# esquema_eletrico_eagle.net
KiCad netlist of a schematic drawn in EAGLE
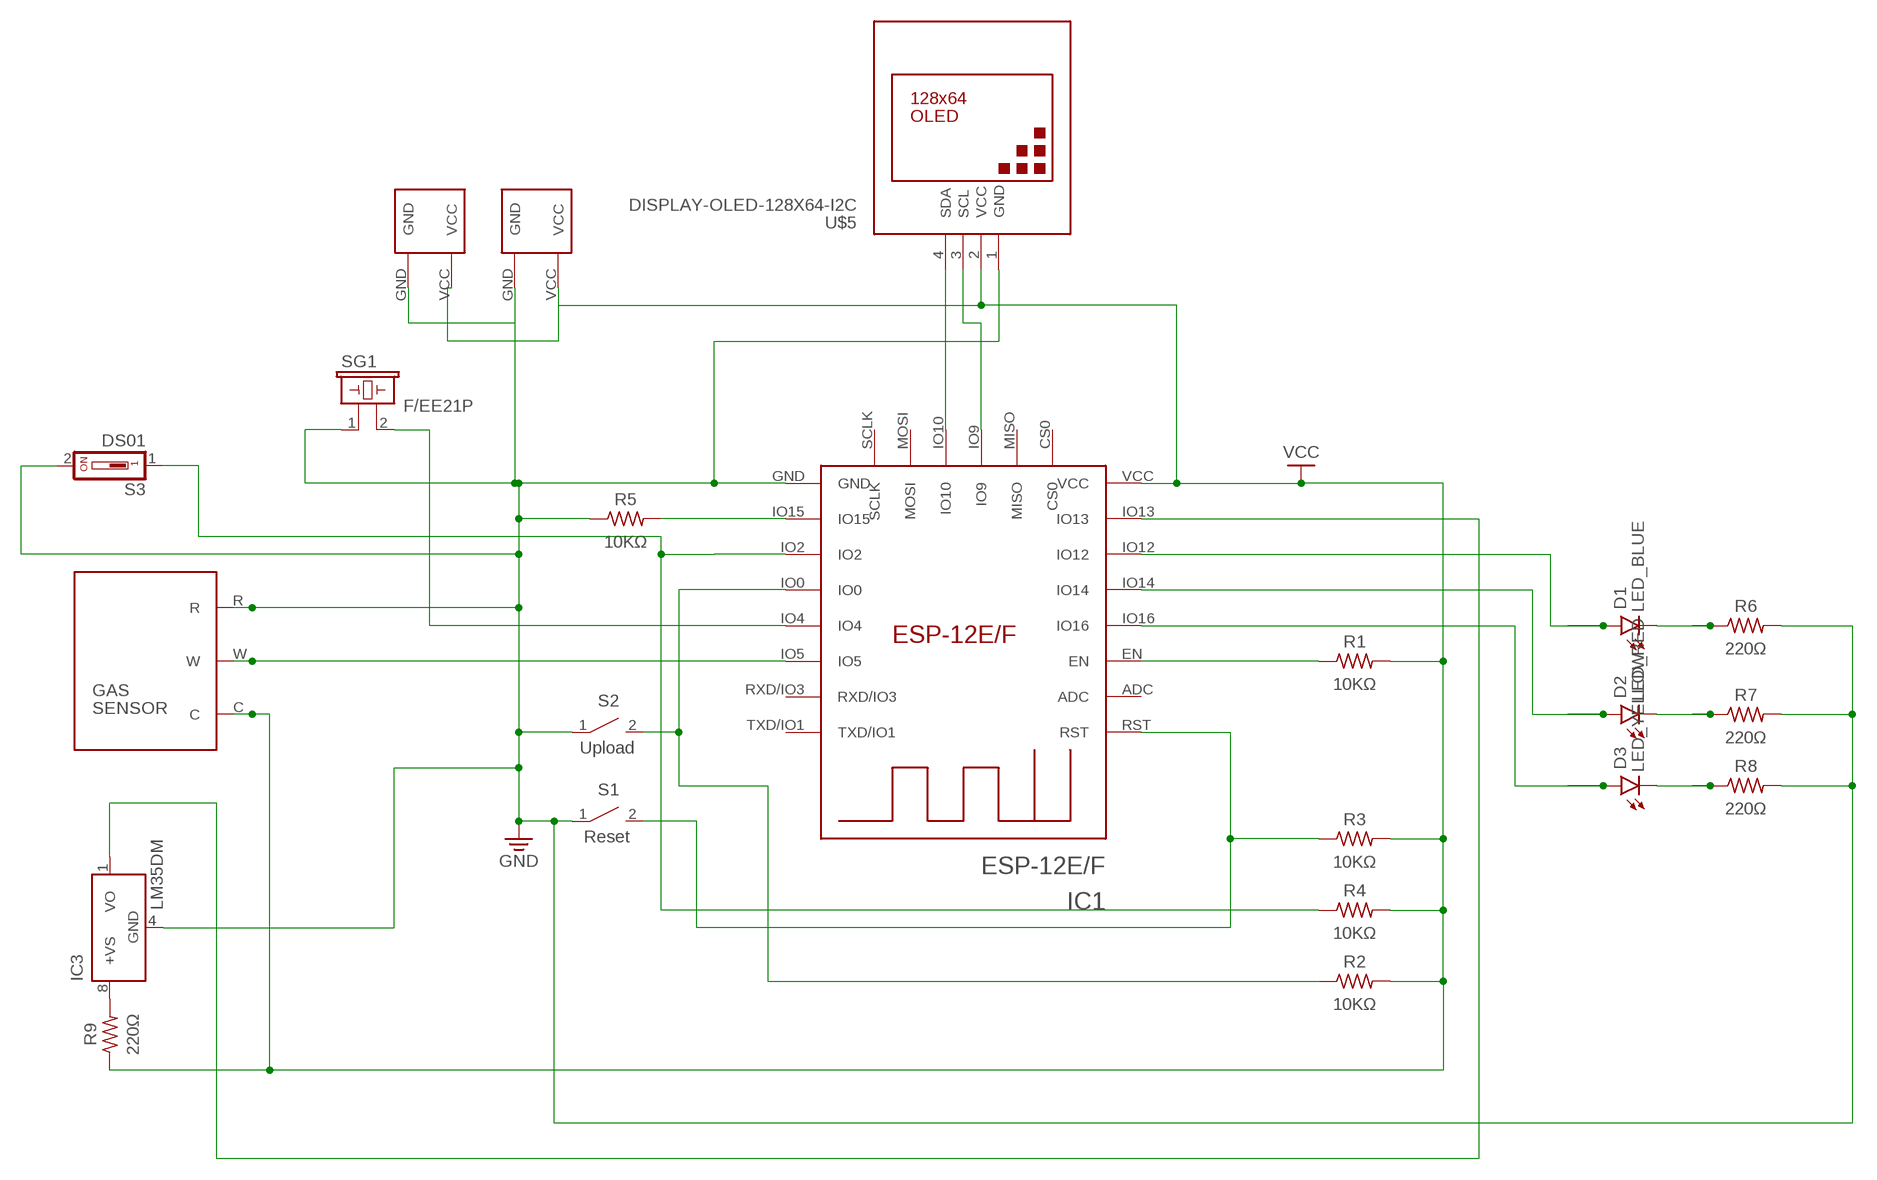
[diagram p0: schematic, sheet 1]

(export (version "E")
  (design (tool "Eeschema 10.0.6"))
  (components
    (comp (ref "D1")
      (value "LED_BLUE")
      (footprint "eagle-import:LEDRD254W60D565H860B_B")
      (libsource (lib "eagle-import") (part "LED_RADIALBLUE_"))
    )
    (comp (ref "D2")
      (value "LED_RED")
      (footprint "eagle-import:LEDRD254W60D565H860B")
      (libsource (lib "eagle-import") (part "LED_RADIALRED_"))
    )
    (comp (ref "D3")
      (value "LED_YELLOW")
      (footprint "eagle-import:LEDRD254W60D565H860B_Y")
      (libsource (lib "eagle-import") (part "LED_RADIALYELLOW_"))
    )
    (comp (ref "IC1")
      (value "ESP-12E/F")
      (footprint "eagle-import:ESP-12E")
      (libsource (lib "eagle-import") (part "ESP-12E/F"))
    )
    (comp (ref "IC3")
      (value "LM35DM")
      (footprint "eagle-import:SO08")
      (libsource (lib "eagle-import") (part "LM35DM"))
    )
    (comp (ref "R1")
      (value "10KΩ")
      (footprint "eagle-import:RESAD724W46L381D178B")
      (libsource (lib "eagle-import") (part "R-USAXIAL-7.2MM-PITCH_"))
    )
    (comp (ref "R2")
      (value "10KΩ")
      (footprint "eagle-import:RESAD724W46L381D178B")
      (libsource (lib "eagle-import") (part "R-USAXIAL-7.2MM-PITCH_"))
    )
    (comp (ref "R3")
      (value "10KΩ")
      (footprint "eagle-import:RESAD724W46L381D178B")
      (libsource (lib "eagle-import") (part "R-USAXIAL-7.2MM-PITCH_"))
    )
    (comp (ref "R4")
      (value "10KΩ")
      (footprint "eagle-import:RESAD724W46L381D178B")
      (libsource (lib "eagle-import") (part "R-USAXIAL-7.2MM-PITCH_"))
    )
    (comp (ref "R5")
      (value "10KΩ")
      (footprint "eagle-import:RESAD724W46L381D178B")
      (libsource (lib "eagle-import") (part "R-USAXIAL-7.2MM-PITCH_"))
    )
    (comp (ref "R6")
      (value "220Ω")
      (footprint "eagle-import:RESAD724W46L381D178B")
      (libsource (lib "eagle-import") (part "R-USAXIAL-7.2MM-PITCH_"))
    )
    (comp (ref "R7")
      (value "220Ω")
      (footprint "eagle-import:RESAD724W46L381D178B")
      (libsource (lib "eagle-import") (part "R-USAXIAL-7.2MM-PITCH_"))
    )
    (comp (ref "R8")
      (value "220Ω")
      (footprint "eagle-import:RESAD724W46L381D178B")
      (libsource (lib "eagle-import") (part "R-USAXIAL-7.2MM-PITCH_"))
    )
    (comp (ref "R9")
      (value "220Ω")
      (footprint "eagle-import:RESAD724W46L381D178B")
      (libsource (lib "eagle-import") (part "R-USAXIAL-7.2MM-PITCH_"))
    )
    (comp (ref "S1")
      (value "Reset")
      (footprint "eagle-import:B3U-1000P(M)-B")
      (fields (field (name "MANUFACTURER") "OMRON"))
      (libsource (lib "eagle-import") (part "B3U-X0001000P(M)-BB3U-1000P(M)-B"))
    )
    (comp (ref "S2")
      (value "Upload")
      (footprint "eagle-import:B3U-1000P(M)-B")
      (fields (field (name "MANUFACTURER") "OMRON"))
      (libsource (lib "eagle-import") (part "B3U-X0001000P(M)-BB3U-1000P(M)-B"))
    )
    (comp (ref "S3")
      (value "DS01")
      (footprint "eagle-import:DS-01")
      (libsource (lib "eagle-import") (part "DS01"))
    )
    (comp (ref "SG1")
      (value "F/EE21P")
      (footprint "eagle-import:F_EE21P")
      (libsource (lib "eagle-import") (part "F/EE21P"))
    )
    (comp (ref "U$1")
      (value "CR2032")
      (footprint "eagle-import:CR2032-20MM")
      (libsource (lib "eagle-import") (part "CR2032"))
    )
    (comp (ref "U$2")
      (value "3-ELECTRODE-GAS-SENSOR")
      (footprint "eagle-import:3-ELECTRODE")
      (fields (field (name "MANUFACTURER") "Wearnes Cambion"))
      (libsource (lib "eagle-import") (part "3-ELECTRODE-GAS-SENSOR"))
    )
    (comp (ref "U$3")
      (value "CR2032")
      (footprint "eagle-import:CR2032-20MM")
      (libsource (lib "eagle-import") (part "CR2032"))
    )
    (comp (ref "U$5")
      (value "DISPLAY-OLED-128X64-I2C")
      (footprint "eagle-import:DISPLAY-OLED-128X64-I2C")
      (libsource (lib "eagle-import") (part "DISPLAY-OLED-128X64-I2C"))
    )
  )
  (nets
    (net (code "1") (name "GND") (class "Default")
      (node (ref "IC1") (pin "GND") (pinfunction "GND_GND") (pintype "power_in"))
      (node (ref "IC3") (pin "4") (pinfunction "GND_4") (pintype "power_in"))
      (node (ref "R5") (pin "1") (pinfunction "1_1") (pintype "passive"))
      (node (ref "R6") (pin "2") (pinfunction "2_2") (pintype "passive"))
      (node (ref "R7") (pin "2") (pinfunction "2_2") (pintype "passive"))
      (node (ref "R8") (pin "2") (pinfunction "2_2") (pintype "passive"))
      (node (ref "S1") (pin "1") (pinfunction "1_1") (pintype "bidirectional"))
      (node (ref "S2") (pin "1") (pinfunction "1_1") (pintype "bidirectional"))
      (node (ref "S3") (pin "2") (pinfunction "2_2") (pintype "passive"))
      (node (ref "SG1") (pin "1") (pinfunction "1_1") (pintype "passive"))
      (node (ref "U$1") (pin "GND") (pinfunction "GND_GND") (pintype "bidirectional"))
      (node (ref "U$2") (pin "R") (pinfunction "R_R") (pintype "bidirectional"))
      (node (ref "U$3") (pin "GND") (pinfunction "GND_GND") (pintype "bidirectional"))
      (node (ref "U$5") (pin "1") (pinfunction "GND_1") (pintype "power_in"))
    )
    (net (code "2") (name "Net-(D1-A)") (class "Default")
      (node (ref "D1") (pin "1") (pinfunction "A_1") (pintype "passive"))
      (node (ref "IC1") (pin "IO12") (pinfunction "IO12_IO12") (pintype "bidirectional"))
    )
    (net (code "3") (name "Net-(D1-C)") (class "Default")
      (node (ref "D1") (pin "2") (pinfunction "C_2") (pintype "passive"))
      (node (ref "R6") (pin "1") (pinfunction "1_1") (pintype "passive"))
    )
    (net (code "4") (name "Net-(D2-A)") (class "Default")
      (node (ref "D2") (pin "1") (pinfunction "A_1") (pintype "passive"))
      (node (ref "IC1") (pin "IO14") (pinfunction "IO14_IO14") (pintype "bidirectional"))
    )
    (net (code "5") (name "Net-(D2-C)") (class "Default")
      (node (ref "D2") (pin "2") (pinfunction "C_2") (pintype "passive"))
      (node (ref "R7") (pin "1") (pinfunction "1_1") (pintype "passive"))
    )
    (net (code "6") (name "Net-(D3-A)") (class "Default")
      (node (ref "D3") (pin "1") (pinfunction "A_1") (pintype "passive"))
      (node (ref "IC1") (pin "IO16") (pinfunction "IO16_IO16") (pintype "bidirectional"))
    )
    (net (code "7") (name "Net-(D3-C)") (class "Default")
      (node (ref "D3") (pin "2") (pinfunction "C_2") (pintype "passive"))
      (node (ref "R8") (pin "1") (pinfunction "1_1") (pintype "passive"))
    )
    (net (code "8") (name "Net-(IC1-PadEN)") (class "Default")
      (node (ref "IC1") (pin "EN") (pinfunction "EN_EN") (pintype "bidirectional"))
      (node (ref "R1") (pin "1") (pinfunction "1_1") (pintype "passive"))
    )
    (net (code "9") (name "Net-(IC1-PadIO0)") (class "Default")
      (node (ref "IC1") (pin "IO0") (pinfunction "IO0_IO0") (pintype "bidirectional"))
      (node (ref "R2") (pin "1") (pinfunction "1_1") (pintype "passive"))
      (node (ref "S2") (pin "2") (pinfunction "2_2") (pintype "bidirectional"))
    )
    (net (code "10") (name "Net-(IC1-PadIO2)") (class "Default")
      (node (ref "IC1") (pin "IO2") (pinfunction "IO2_IO2") (pintype "bidirectional"))
      (node (ref "R4") (pin "1") (pinfunction "1_1") (pintype "passive"))
      (node (ref "S3") (pin "1") (pinfunction "1_1") (pintype "passive"))
    )
    (net (code "11") (name "Net-(IC1-PadIO4)") (class "Default")
      (node (ref "IC1") (pin "IO4") (pinfunction "IO4_IO4") (pintype "bidirectional"))
      (node (ref "SG1") (pin "2") (pinfunction "2_2") (pintype "passive"))
    )
    (net (code "12") (name "Net-(IC1-PadIO5)") (class "Default")
      (node (ref "IC1") (pin "IO5") (pinfunction "IO5_IO5") (pintype "bidirectional"))
      (node (ref "U$2") (pin "W") (pinfunction "W_W") (pintype "bidirectional"))
    )
    (net (code "13") (name "Net-(IC1-PadIO15)") (class "Default")
      (node (ref "IC1") (pin "IO15") (pinfunction "IO15_IO15") (pintype "bidirectional"))
      (node (ref "R5") (pin "2") (pinfunction "2_2") (pintype "passive"))
    )
    (net (code "14") (name "Net-(IC1-PadRST)") (class "Default")
      (node (ref "IC1") (pin "RST") (pinfunction "RST_RST") (pintype "input"))
      (node (ref "R3") (pin "1") (pinfunction "1_1") (pintype "passive"))
      (node (ref "S1") (pin "2") (pinfunction "2_2") (pintype "bidirectional"))
    )
    (net (code "15") (name "Net-(IC3-+VS)") (class "Default")
      (node (ref "IC3") (pin "8") (pinfunction "+VS_8") (pintype "input"))
      (node (ref "R9") (pin "2") (pinfunction "2_2") (pintype "passive"))
    )
    (net (code "16") (name "Net-(IC3-VO)") (class "Default")
      (node (ref "IC1") (pin "IO13") (pinfunction "IO13_IO13") (pintype "bidirectional"))
      (node (ref "IC3") (pin "1") (pinfunction "VO_1") (pintype "input"))
    )
    (net (code "17") (name "Net-(U$5-SCL)") (class "Default")
      (node (ref "IC1") (pin "IO9") (pinfunction "IO9_IO9") (pintype "bidirectional"))
      (node (ref "U$5") (pin "3") (pinfunction "SCL_3") (pintype "bidirectional"))
    )
    (net (code "18") (name "Net-(U$5-SDA)") (class "Default")
      (node (ref "IC1") (pin "IO10") (pinfunction "IO10_IO10") (pintype "bidirectional"))
      (node (ref "U$5") (pin "4") (pinfunction "SDA_4") (pintype "bidirectional"))
    )
    (net (code "19") (name "VCC") (class "Default")
      (node (ref "IC1") (pin "VCC") (pinfunction "VCC_VCC") (pintype "power_in"))
      (node (ref "R1") (pin "2") (pinfunction "2_2") (pintype "passive"))
      (node (ref "R2") (pin "2") (pinfunction "2_2") (pintype "passive"))
      (node (ref "R3") (pin "2") (pinfunction "2_2") (pintype "passive"))
      (node (ref "R4") (pin "2") (pinfunction "2_2") (pintype "passive"))
      (node (ref "R9") (pin "1") (pinfunction "1_1") (pintype "passive"))
      (node (ref "U$1") (pin "VCC") (pinfunction "VCC_VCC") (pintype "bidirectional"))
      (node (ref "U$2") (pin "C") (pinfunction "C_C") (pintype "bidirectional"))
      (node (ref "U$3") (pin "VCC") (pinfunction "VCC_VCC") (pintype "bidirectional"))
      (node (ref "U$5") (pin "2") (pinfunction "VCC_2") (pintype "power_in"))
    )
    (net (code "20") (name "unconnected-(IC1-PadADC)") (class "Default")
      (node (ref "IC1") (pin "ADC") (pinfunction "ADC_ADC") (pintype "bidirectional"))
    )
    (net (code "21") (name "unconnected-(IC1-PadCS0)") (class "Default")
      (node (ref "IC1") (pin "CS0") (pinfunction "CS0_CS0") (pintype "bidirectional"))
    )
    (net (code "22") (name "unconnected-(IC1-PadMISO)") (class "Default")
      (node (ref "IC1") (pin "MISO") (pinfunction "MISO_MISO") (pintype "bidirectional"))
    )
    (net (code "23") (name "unconnected-(IC1-PadMOSI)") (class "Default")
      (node (ref "IC1") (pin "MOSI") (pinfunction "MOSI_MOSI") (pintype "bidirectional"))
    )
    (net (code "24") (name "unconnected-(IC1-PadRXD{slash}IO3)") (class "Default")
      (node (ref "IC1") (pin "RXD/IO3") (pinfunction "RXD/IO3_RXD/IO3") (pintype "bidirectional"))
    )
    (net (code "25") (name "unconnected-(IC1-PadSCLK)") (class "Default")
      (node (ref "IC1") (pin "SCLK") (pinfunction "SCLK_SCLK") (pintype "bidirectional"))
    )
    (net (code "26") (name "unconnected-(IC1-PadTXD{slash}IO1)") (class "Default")
      (node (ref "IC1") (pin "TXD/IO1") (pinfunction "TXD/IO1_TXD/IO1") (pintype "bidirectional"))
    )
  )
)
